# kilafors_rev_a.net
KiCad netlist of a schematic drawn in EAGLE
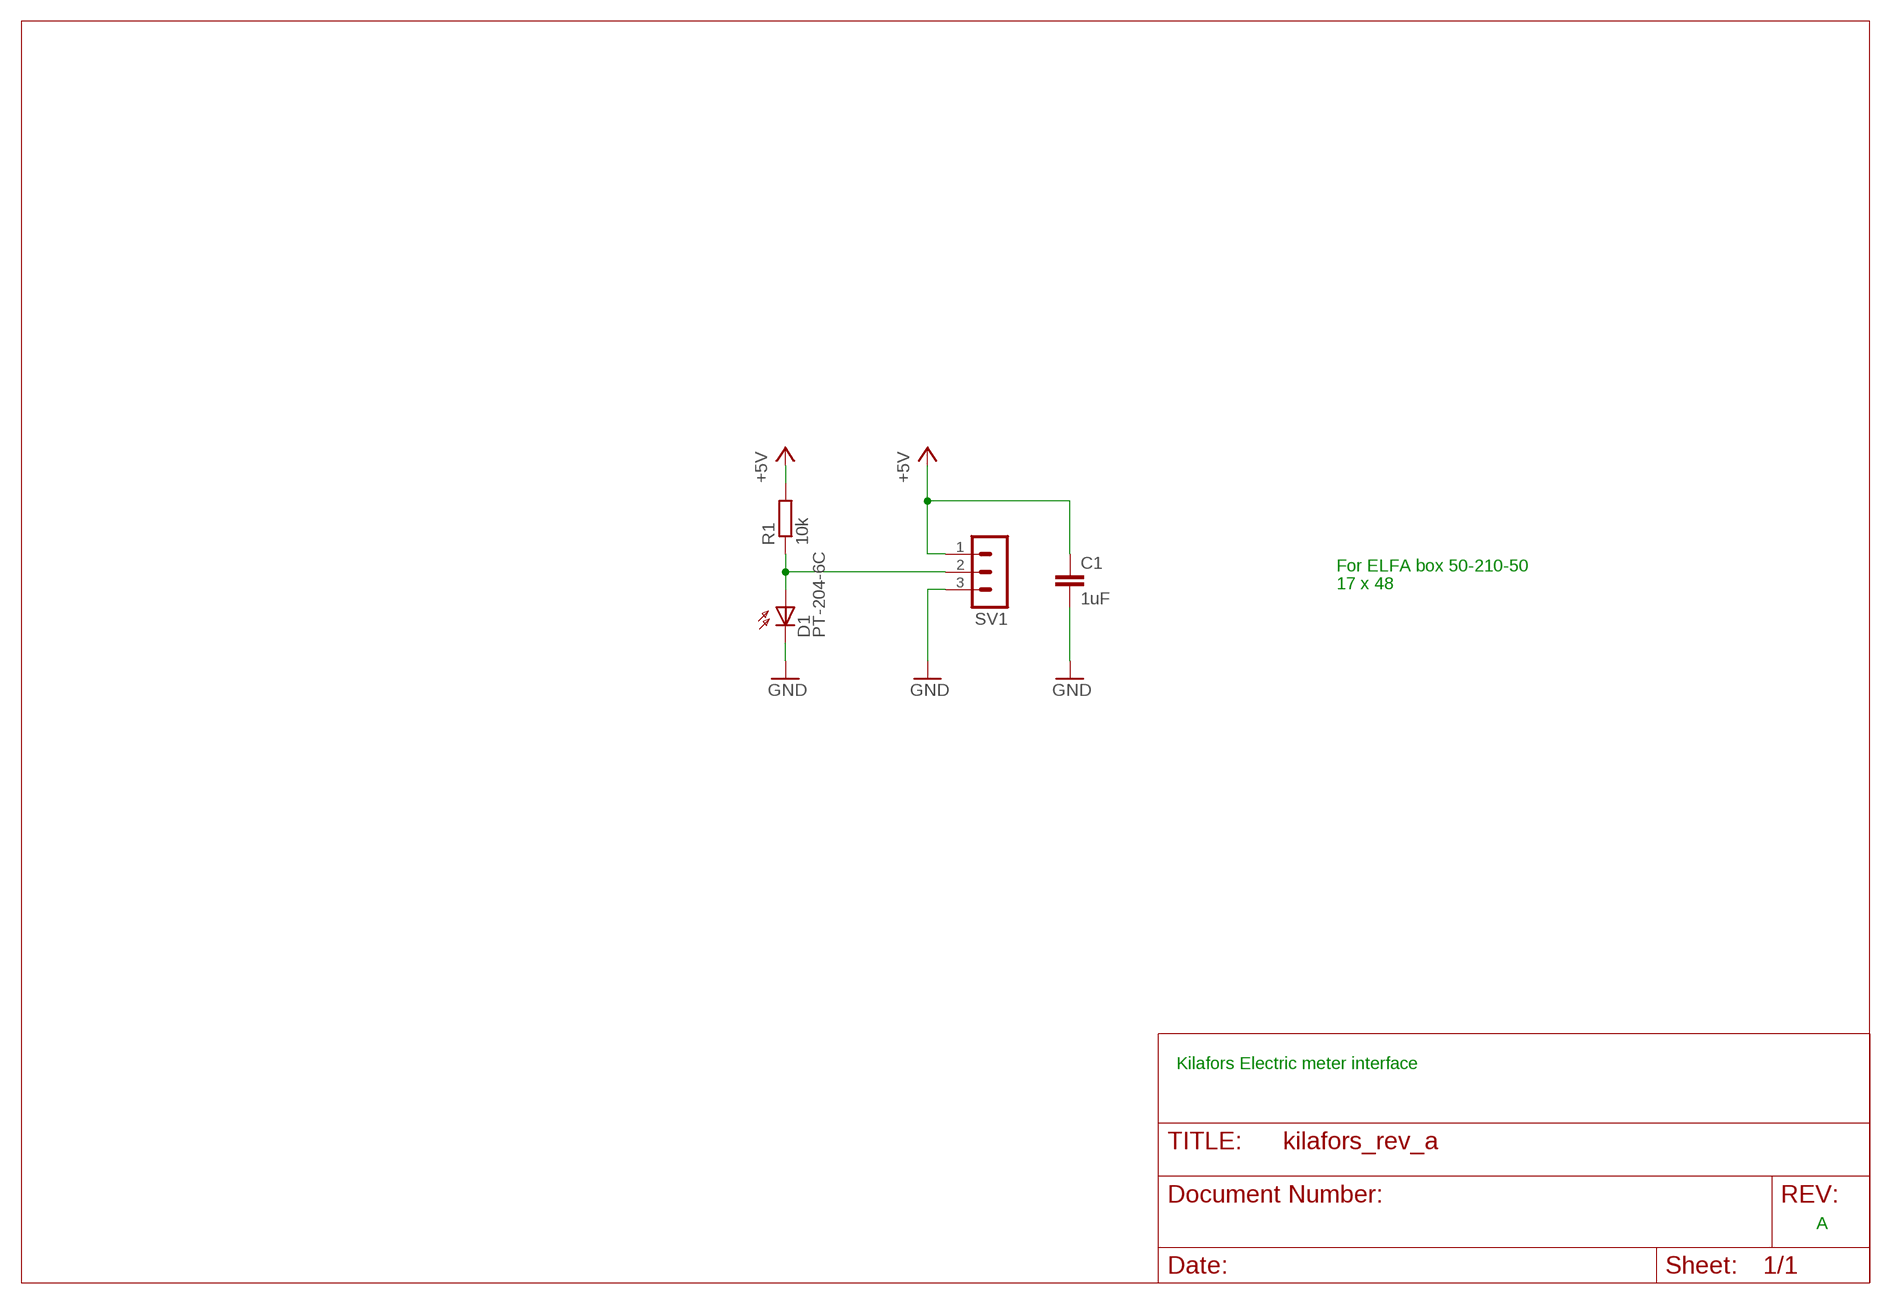
[diagram p0: schematic, sheet 1]

(export (version "E")
  (design (tool "Eeschema 10.0.6"))
  (components
    (comp (ref "C1")
      (value "1uF")
      (footprint "eagle-import:C0805")
      (libsource (lib "eagle-import") (part "C-EUC0805"))
    )
    (comp (ref "D1")
      (value "PT-204-6C")
      (footprint "eagle-import:BP104")
      (fields (field (name "MF") "VISHAY/TELEFUNKEN") (field (name "MPN") "BP104"))
      (libsource (lib "eagle-import") (part "BP104"))
    )
    (comp (ref "R1")
      (value "10k")
      (footprint "eagle-import:R0805")
      (libsource (lib "eagle-import") (part "R-EU_R0805"))
    )
    (comp (ref "SV1")
      (value "MA03-1")
      (footprint "eagle-import:MA03-1")
      (libsource (lib "eagle-import") (part "MA03-1"))
    )
  )
  (nets
    (net (code "1") (name "+5V") (class "Default")
      (node (ref "C1") (pin "1") (pinfunction "1_1") (pintype "passive"))
      (node (ref "R1") (pin "2") (pinfunction "2_2") (pintype "passive"))
      (node (ref "SV1") (pin "1") (pinfunction "1_1") (pintype "passive"))
    )
    (net (code "2") (name "GND") (class "Default")
      (node (ref "C1") (pin "2") (pinfunction "2_2") (pintype "passive"))
      (node (ref "D1") (pin "K") (pinfunction "C_K") (pintype "passive"))
      (node (ref "SV1") (pin "3") (pinfunction "3_3") (pintype "passive"))
    )
    (net (code "3") (name "Net-(D1-PadA)") (class "Default")
      (node (ref "D1") (pin "A") (pinfunction "A_A") (pintype "passive"))
      (node (ref "R1") (pin "1") (pinfunction "1_1") (pintype "passive"))
      (node (ref "SV1") (pin "2") (pinfunction "2_2") (pintype "passive"))
    )
  )
)
